# Integrater.net
KiCad netlist of a schematic drawn in Altium Designer
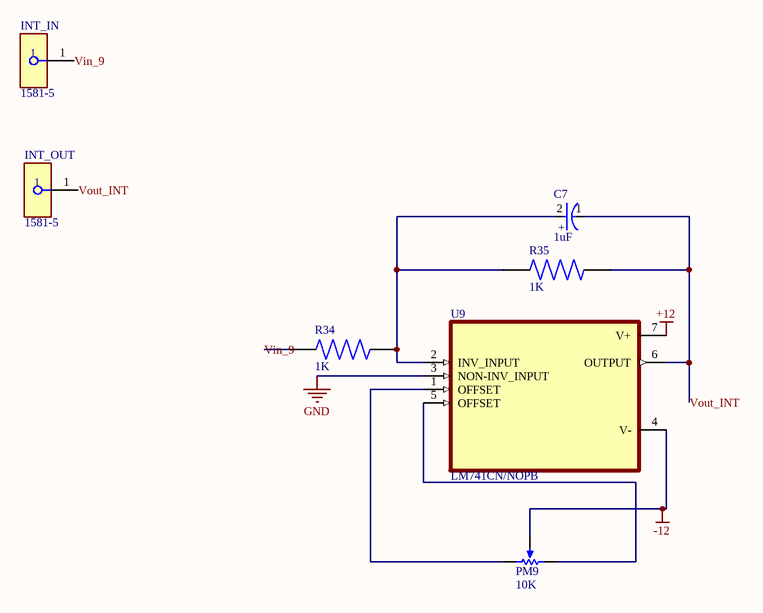
[diagram p0: Integrater.SchDoc]

(export (version "E")
  (design (tool "Eeschema 10.0.6"))
  (components
    (comp (ref "C7")
      (value "1uF")
      (footprint "FP-ECA-2CHG010I-MFG")
      (description "CAP ALUM 1UF 20% 160V RADIAL")
      (fields (field (name "TOLERANCE") "20%"))
      (libsource (lib "Altium Content Vault") (part "a00bbbee19879c290e62620ae7e47b1"))
    )
    (comp (ref "INT_IN")
      (value "1581-5")
      (footprint "FP-1581-5-MFG")
      (description "CONN BANANA JACK TURRET GREEN")
      (libsource (lib "Altium Content Vault") (part "c5c826e0c4b67fe3b42ef77f2d4decc"))
    )
    (comp (ref "INT_OUT")
      (value "1581-5")
      (footprint "FP-1581-5-MFG")
      (description "CONN BANANA JACK TURRET GREEN")
      (libsource (lib "Altium Content Vault") (part "c5c826e0c4b67fe3b42ef77f2d4decc"))
    )
    (comp (ref "PM9")
      (value "10K")
      (footprint "PCBComponent_1")
      (libsource (lib "Integrated_Library1") (part "Component_1"))
    )
    (comp (ref "R34")
      (value "1K")
      (footprint "RESAD1100W55L680D260")
      (description "1.07 kOhms Â±1% 0.25W, 1/4W Through Hole Resistor Axial - Metal Film")
      (fields (field (name "MF") "Yageo") (field (name "MP") "MFR-25FBF52-1K"))
      (libsource (lib "MFR-25FBF52-1K") (part "MFR-25FBF52-1K"))
    )
    (comp (ref "R35")
      (value "1K")
      (footprint "RESAD1100W55L680D260")
      (description "1.07 kOhms Â±1% 0.25W, 1/4W Through Hole Resistor Axial - Metal Film")
      (fields (field (name "MF") "Yageo") (field (name "MP") "MFR-25FBF52-1K"))
      (libsource (lib "MFR-25FBF52-1K") (part "MFR-25FBF52-1K"))
    )
    (comp (ref "U9")
      (value "LM741CN/NOPB")
      (footprint "DIP794W45P254L959H508Q8")
      (description "Single, 44-V, 1-MHz operational amplifier")
      (fields (field (name "MF") "Texas Instruments"))
      (libsource (lib "LM741CN_NOPB (1)") (part "LM741CN/NOPB"))
    )
  )
  (nets
    (net (code "1") (name "+12") (class "Default")
      (node (ref "U9") (pin "7") (pinfunction "V+_7") (pintype "power_in"))
    )
    (net (code "2") (name "-12") (class "Default")
      (node (ref "PM9") (pin "2") (pinfunction "S_2") (pintype "passive"))
      (node (ref "U9") (pin "4") (pinfunction "V-_4") (pintype "power_in"))
    )
    (net (code "3") (name "/Vin_9") (class "Default")
      (node (ref "INT_IN") (pin "1") (pinfunction "1_1") (pintype "passive"))
      (node (ref "R34") (pin "1") (pinfunction "1_1") (pintype "passive"))
    )
    (net (code "4") (name "/Vout_INT") (class "Default")
      (node (ref "C7") (pin "1") (pinfunction "C_1") (pintype "passive"))
      (node (ref "INT_OUT") (pin "1") (pinfunction "1_1") (pintype "passive"))
      (node (ref "R35") (pin "2") (pinfunction "2_2") (pintype "passive"))
      (node (ref "U9") (pin "6") (pinfunction "OUTPUT_6") (pintype "output"))
    )
    (net (code "5") (name "GND") (class "Default")
      (node (ref "U9") (pin "3") (pinfunction "NON-INV_INPUT_3") (pintype "input"))
    )
    (net (code "6") (name "Net-(C7-A)") (class "Default")
      (node (ref "C7") (pin "2") (pinfunction "A_2") (pintype "passive"))
      (node (ref "R34") (pin "2") (pinfunction "2_2") (pintype "passive"))
      (node (ref "R35") (pin "1") (pinfunction "1_1") (pintype "passive"))
      (node (ref "U9") (pin "2") (pinfunction "INV_INPUT_2") (pintype "input"))
    )
    (net (code "7") (name "Net-(PM9-CCW)") (class "Default")
      (node (ref "PM9") (pin "1") (pinfunction "CCW_1") (pintype "passive"))
      (node (ref "U9") (pin "5") (pinfunction "OFFSET_5") (pintype "input"))
    )
    (net (code "8") (name "Net-(PM9-CW)") (class "Default")
      (node (ref "PM9") (pin "3") (pinfunction "CW_3") (pintype "passive"))
      (node (ref "U9") (pin "1") (pinfunction "OFFSET_1") (pintype "input"))
    )
  )
)
